# final.net
KiCad netlist of a schematic drawn in Altium Designer
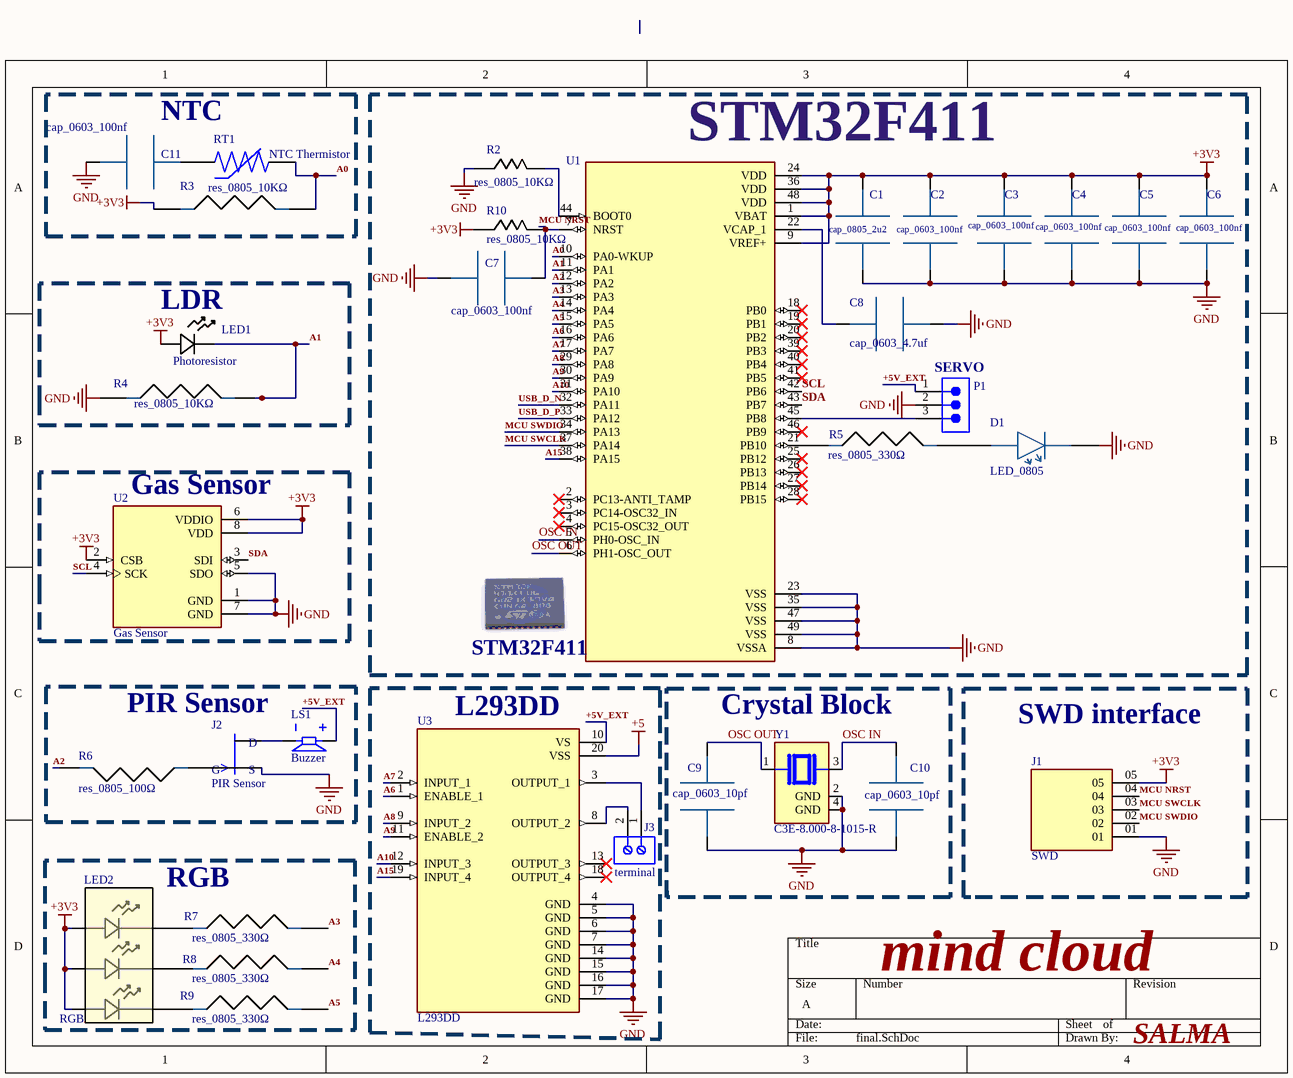
[diagram p0: final.SchDoc]

(export (version "E")
  (design (tool "Eeschema 10.0.6"))
  (components
    (comp (ref "C1")
      (value "cap_0805_2u2")
      (footprint "capa0805")
      (fields (field (name "MFR") "Samsung Electro-Mechanics") (field (name "MFR PART") "CL10A225KO8NNNC"))
      (libsource (lib "STM32") (part "cap_0805_2u2"))
    )
    (comp (ref "C2")
      (value "cap_0603_100nf")
      (footprint "capa0805")
      (fields (field (name "MFR") "Samsung Electro-Mechanics") (field (name "MFR PART") "CL10B104KB8NNNC"))
      (libsource (lib "STM32") (part "cap_0603_100nf"))
    )
    (comp (ref "C3")
      (value "cap_0603_100nf")
      (footprint "capa0805")
      (fields (field (name "MFR") "Samsung Electro-Mechanics") (field (name "MFR PART") "CL10B104KB8NNNC"))
      (libsource (lib "STM32") (part "cap_0603_100nf"))
    )
    (comp (ref "C4")
      (value "cap_0603_100nf")
      (footprint "capa0805")
      (fields (field (name "MFR") "Samsung Electro-Mechanics") (field (name "MFR PART") "CL10B104KB8NNNC"))
      (libsource (lib "STM32") (part "cap_0603_100nf"))
    )
    (comp (ref "C5")
      (value "cap_0603_100nf")
      (footprint "capa0805")
      (fields (field (name "MFR") "Samsung Electro-Mechanics") (field (name "MFR PART") "CL10B104KB8NNNC"))
      (libsource (lib "STM32") (part "cap_0603_100nf"))
    )
    (comp (ref "C6")
      (value "cap_0603_100nf")
      (footprint "capa0805")
      (fields (field (name "MFR") "Samsung Electro-Mechanics") (field (name "MFR PART") "CL10B104KB8NNNC"))
      (libsource (lib "STM32") (part "cap_0603_100nf"))
    )
    (comp (ref "C7")
      (value "cap_0603_100nf")
      (footprint "capa0805")
      (fields (field (name "MFR") "Samsung Electro-Mechanics") (field (name "MFR PART") "CL10B104KB8NNNC"))
      (libsource (lib "STM32") (part "cap_0603_100nf"))
    )
    (comp (ref "C8")
      (value "cap_0603_4.7uf")
      (footprint "capa0805")
      (fields (field (name "MFR") "Samsung Electro-Mechanics") (field (name "MFR PART") "CL10A475KP8NNNC"))
      (libsource (lib "STM32") (part "cap_0603_4.7uf"))
    )
    (comp (ref "C9")
      (value "cap_0603_10pf")
      (footprint "capa0805")
      (fields (field (name "MFR") "Samsung Electro-Mechanics") (field (name "MFR PART") "CL10C100JB8NNNC"))
      (libsource (lib "STM32") (part "cap_0603_10pf"))
    )
    (comp (ref "C10")
      (value "cap_0603_10pf")
      (footprint "capa0805")
      (fields (field (name "MFR") "Samsung Electro-Mechanics") (field (name "MFR PART") "CL10C100JB8NNNC"))
      (libsource (lib "STM32") (part "cap_0603_10pf"))
    )
    (comp (ref "C11")
      (value "cap_0603_100nf")
      (footprint "capa0805")
      (fields (field (name "MFR") "Samsung Electro-Mechanics") (field (name "MFR PART") "CL10B104KB8NNNC"))
      (libsource (lib "STM32") (part "cap_0603_100nf"))
    )
    (comp (ref "D1")
      (value "LED_0805")
      (footprint "LED_0805")
      (fields (field (name "MFR") "YONGYUTAI") (field (name "MFR PART") "YLED0805R"))
      (libsource (lib "Schlib final") (part "LED_0805"))
    )
    (comp (ref "J1")
      (value "SWD")
      (footprint "SAMTEC_MTSW-105-07-T-S-165")
      (fields (field (name "MFR") "Samtec") (field (name "MFR PART") "MTSW-105-07-T-S-165"))
      (libsource (lib "STM32") (part "MTSW-105-07-T-S-165"))
    )
    (comp (ref "J2")
      (value "PIR Sensor")
      (footprint "PIR Sensor")
      (fields (field (name "MFR") "Zilog") (field (name "MFR PART") "ZRE200GE"))
      (libsource (lib "Schlib final") (part "PIR Sensor"))
    )
    (comp (ref "J3")
      (value "terminal")
      (footprint "691253900002")
      (description "Terminal Block, 7.5MM Pitch, Vertical, Rising Cage Clamp, 12-30 AWG, 2 Pin")
      (libsource (lib "Altium Content Vault") (part "TBL - 1R - 02P - Screw"))
    )
    (comp (ref "LED1")
      (value "Photoresistor")
      (footprint "Photoresistor")
      (fields (field (name "MFR") "JCHL") (field (name "MFR PART") "GL5528(10-20)"))
      (libsource (lib "Schlib final") (part "Photoresistor"))
    )
    (comp (ref "LED2")
      (value "RGB")
      (footprint "RGB")
      (fields (field (name "MFR") "Broadcom") (field (name "MFR PART") "ASMT-YTD7-0AA02"))
      (libsource (lib "Schlib final") (part "RGB"))
    )
    (comp (ref "LS1")
      (value "Buzzer")
      (footprint "Buzzer")
      (fields (field (name "MFR") "CUI") (field (name "MFR PART") "CMI-1210-5-95T"))
      (libsource (lib "Schlib final") (part "Buzzer"))
    )
    (comp (ref "P1")
      (value "SERVO")
      (footprint "691386700003")
      (description "Terminal Block, 5.00MM, Male Pcb Horizontal/vertical Cab Divisible, 3 Pins")
      (fields (field (name "VOLTAGE") "300V"))
      (libsource (lib "Altium Content Vault") (part "TBL - 1R - 03P - Male"))
    )
    (comp (ref "R2")
      (value "res_0805_10KΩ")
      (footprint "Res_0805")
      (fields (field (name "MFR") "YAGEO") (field (name "MFR PART") "RC0603FR-0710KL"))
      (libsource (lib "Schlib final") (part "res_0805_10KΩ"))
    )
    (comp (ref "R3")
      (value "res_0805_10KΩ")
      (footprint "Res_0805")
      (fields (field (name "MFR") "YAGEO") (field (name "MFR PART") "RC0603FR-0710KL"))
      (libsource (lib "STM32") (part "res_0805_10KΩ"))
    )
    (comp (ref "R4")
      (value "res_0805_10KΩ")
      (footprint "Res_0805")
      (fields (field (name "MFR") "YAGEO") (field (name "MFR PART") "RC0603FR-0710KL"))
      (libsource (lib "STM32") (part "res_0805_10KΩ"))
    )
    (comp (ref "R5")
      (value "res_0805_330Ω")
      (footprint "Res_0805")
      (fields (field (name "MFR") "UNI-ROYAL") (field (name "MFR PART") "0805W8F3300T5E"))
      (libsource (lib "Schlib final") (part "res_0805_330Ω"))
    )
    (comp (ref "R6")
      (value "res_0805_100Ω")
      (footprint "Res_0805")
      (fields (field (name "MFR") "YAGEO") (field (name "MFR PART") "RC0805FR-07100RL"))
      (libsource (lib "Schlib final") (part "res_0805_100Ω"))
    )
    (comp (ref "R7")
      (value "res_0805_330Ω")
      (footprint "Res_0805")
      (fields (field (name "MFR") "UNI-ROYAL") (field (name "MFR PART") "0805W8F3300T5E"))
      (libsource (lib "Schlib final") (part "res_0805_330Ω"))
    )
    (comp (ref "R8")
      (value "res_0805_330Ω")
      (footprint "Res_0805")
      (fields (field (name "MFR") "UNI-ROYAL") (field (name "MFR PART") "0805W8F3300T5E"))
      (libsource (lib "Schlib final") (part "res_0805_330Ω"))
    )
    (comp (ref "R9")
      (value "res_0805_330Ω")
      (footprint "Res_0805")
      (fields (field (name "MFR") "UNI-ROYAL") (field (name "MFR PART") "0805W8F3300T5E"))
      (libsource (lib "Schlib final") (part "res_0805_330Ω"))
    )
    (comp (ref "R10")
      (value "res_0805_10KΩ")
      (footprint "Res_0805")
      (fields (field (name "MFR") "YAGEO") (field (name "MFR PART") "RC0603FR-0710KL"))
      (libsource (lib "Schlib final") (part "res_0805_10KΩ"))
    )
    (comp (ref "RT1")
      (value "NTC Thermistor")
      (footprint "NTC Thermistor")
      (fields (field (name "MFR") "muRata") (field (name "MFR PART") "NCU15WF104D60RC"))
      (libsource (lib "Schlib final") (part "NTC Thermistor"))
    )
    (comp (ref "U1")
      (value "STM32F411")
      (footprint "STM32F411")
      (fields (field (name "MFR") "ST") (field (name "MFR PART") "STM32F411CEU6"))
      (libsource (lib "STM32") (part "STM32F411"))
    )
    (comp (ref "U2")
      (value "Gas Sensor")
      (footprint "Gas Sensor")
      (fields (field (name "MFR") "Bosch") (field (name "MFR PART") "BME688"))
      (libsource (lib "Schlib final") (part "Gas Sensor"))
    )
    (comp (ref "U3")
      (value "L293DD")
      (footprint "L293DD")
      (fields (field (name "MFR") "ST"))
      (libsource (lib "Schlib final") (part "L293DD"))
    )
    (comp (ref "Y1")
      (value "C3E-8.000-8-1015-R")
      (footprint "C3E-8.000-8-1015-R")
      (fields (field (name "MFR") "AKER"))
      (libsource (lib "STM32") (part "C3E-8.000-8-1015-R"))
    )
  )
  (nets
    (net (code "1") (name "+3V3") (class "Default")
      (node (ref "C1") (pin "2") (pinfunction "2_2") (pintype "passive"))
      (node (ref "C2") (pin "2") (pinfunction "2_2") (pintype "passive"))
      (node (ref "C3") (pin "2") (pinfunction "2_2") (pintype "passive"))
      (node (ref "C4") (pin "2") (pinfunction "2_2") (pintype "passive"))
      (node (ref "C5") (pin "2") (pinfunction "2_2") (pintype "passive"))
      (node (ref "C6") (pin "2") (pinfunction "2_2") (pintype "passive"))
      (node (ref "J1") (pin "05") (pinfunction "05_05") (pintype "passive"))
      (node (ref "LED1") (pin "2") (pinfunction "ANODE_2") (pintype "passive"))
      (node (ref "LED2") (pin "1") (pinfunction "1_1") (pintype "passive"))
      (node (ref "LED2") (pin "2") (pinfunction "2_2") (pintype "passive"))
      (node (ref "LED2") (pin "3") (pinfunction "3_3") (pintype "passive"))
      (node (ref "R10") (pin "1") (pinfunction "1_1") (pintype "passive"))
      (node (ref "R3") (pin "1") (pinfunction "1_1") (pintype "passive"))
      (node (ref "U1") (pin "1") (pinfunction "VBAT_1") (pintype "power_in"))
      (node (ref "U1") (pin "24") (pinfunction "VDD_24") (pintype "power_in"))
      (node (ref "U1") (pin "36") (pinfunction "VDD_36") (pintype "power_in"))
      (node (ref "U1") (pin "48") (pinfunction "VDD_48") (pintype "power_in"))
      (node (ref "U1") (pin "9") (pinfunction "VREF+_9") (pintype "power_in"))
      (node (ref "U2") (pin "2") (pinfunction "CSB_2") (pintype "input"))
      (node (ref "U2") (pin "6") (pinfunction "VDDIO_6") (pintype "power_in"))
      (node (ref "U2") (pin "8") (pinfunction "VDD_8") (pintype "power_in"))
    )
    (net (code "2") (name "+5") (class "Default")
      (node (ref "U3") (pin "20") (pinfunction "VSS_20") (pintype "power_in"))
    )
    (net (code "3") (name "/+5V_EXT") (class "Default")
      (node (ref "LS1") (pin "P") (pinfunction "P_P") (pintype "passive"))
      (node (ref "P1") (pin "1") (pinfunction "1_1") (pintype "passive"))
      (node (ref "U3") (pin "10") (pinfunction "VS_10") (pintype "power_in"))
    )
    (net (code "4") (name "/A0") (class "Default")
      (node (ref "R3") (pin "2") (pinfunction "2_2") (pintype "passive"))
      (node (ref "RT1") (pin "2") (pinfunction "2_2") (pintype "passive"))
      (node (ref "U1") (pin "10") (pinfunction "PA0-WKUP_10") (pintype "bidirectional"))
    )
    (net (code "5") (name "/A1") (class "Default")
      (node (ref "LED1") (pin "1") (pinfunction "CATHODE_1") (pintype "passive"))
      (node (ref "R4") (pin "2") (pinfunction "2_2") (pintype "passive"))
      (node (ref "U1") (pin "11") (pinfunction "PA1_11") (pintype "bidirectional"))
    )
    (net (code "6") (name "/A2") (class "Default")
      (node (ref "R6") (pin "2") (pinfunction "2_2") (pintype "passive"))
      (node (ref "U1") (pin "12") (pinfunction "PA2_12") (pintype "bidirectional"))
    )
    (net (code "7") (name "/A3") (class "Default")
      (node (ref "R7") (pin "2") (pinfunction "2_2") (pintype "passive"))
      (node (ref "U1") (pin "13") (pinfunction "PA3_13") (pintype "bidirectional"))
    )
    (net (code "8") (name "/A4") (class "Default")
      (node (ref "R8") (pin "2") (pinfunction "2_2") (pintype "passive"))
      (node (ref "U1") (pin "14") (pinfunction "PA4_14") (pintype "bidirectional"))
    )
    (net (code "9") (name "/A5") (class "Default")
      (node (ref "R9") (pin "2") (pinfunction "2_2") (pintype "passive"))
      (node (ref "U1") (pin "15") (pinfunction "PA5_15") (pintype "bidirectional"))
    )
    (net (code "10") (name "/A6") (class "Default")
      (node (ref "U1") (pin "16") (pinfunction "PA6_16") (pintype "bidirectional"))
      (node (ref "U3") (pin "1") (pinfunction "ENABLE_1_1") (pintype "input"))
    )
    (net (code "11") (name "/A7") (class "Default")
      (node (ref "U1") (pin "17") (pinfunction "PA7_17") (pintype "bidirectional"))
      (node (ref "U3") (pin "2") (pinfunction "INPUT_1_2") (pintype "input"))
    )
    (net (code "12") (name "/A8") (class "Default")
      (node (ref "U1") (pin "29") (pinfunction "PA8_29") (pintype "bidirectional"))
      (node (ref "U3") (pin "9") (pinfunction "INPUT_2_9") (pintype "input"))
    )
    (net (code "13") (name "/A9") (class "Default")
      (node (ref "U1") (pin "30") (pinfunction "PA9_30") (pintype "bidirectional"))
      (node (ref "U3") (pin "11") (pinfunction "ENABLE_2_11") (pintype "input"))
    )
    (net (code "14") (name "/A10") (class "Default")
      (node (ref "U1") (pin "31") (pinfunction "PA10_31") (pintype "bidirectional"))
      (node (ref "U3") (pin "12") (pinfunction "INPUT_3_12") (pintype "input"))
    )
    (net (code "15") (name "/A15") (class "Default")
      (node (ref "U1") (pin "38") (pinfunction "PA15_38") (pintype "bidirectional"))
      (node (ref "U3") (pin "19") (pinfunction "INPUT_4_19") (pintype "input"))
    )
    (net (code "16") (name "/MCU NRST") (class "Default")
      (node (ref "C7") (pin "2") (pinfunction "2_2") (pintype "passive"))
      (node (ref "J1") (pin "04") (pinfunction "04_04") (pintype "passive"))
      (node (ref "R10") (pin "2") (pinfunction "2_2") (pintype "passive"))
      (node (ref "U1") (pin "7") (pinfunction "NRST_7") (pintype "bidirectional"))
    )
    (net (code "17") (name "/MCU SWCLK") (class "Default")
      (node (ref "J1") (pin "03") (pinfunction "03_03") (pintype "passive"))
      (node (ref "U1") (pin "37") (pinfunction "PA14_37") (pintype "bidirectional"))
    )
    (net (code "18") (name "/MCU SWDIO") (class "Default")
      (node (ref "J1") (pin "02") (pinfunction "02_02") (pintype "passive"))
      (node (ref "U1") (pin "34") (pinfunction "PA13_34") (pintype "bidirectional"))
    )
    (net (code "19") (name "/OSC IN") (class "Default")
      (node (ref "C10") (pin "2") (pinfunction "2_2") (pintype "passive"))
      (node (ref "U1") (pin "5") (pinfunction "PH0-OSC_IN_5") (pintype "bidirectional"))
      (node (ref "Y1") (pin "3") (pinfunction "2_3") (pintype "passive"))
    )
    (net (code "20") (name "/OSC OUT") (class "Default")
      (node (ref "C9") (pin "2") (pinfunction "2_2") (pintype "passive"))
      (node (ref "U1") (pin "6") (pinfunction "PH1-OSC_OUT_6") (pintype "bidirectional"))
      (node (ref "Y1") (pin "1") (pinfunction "1_1") (pintype "passive"))
    )
    (net (code "21") (name "/SCL") (class "Default")
      (node (ref "U1") (pin "42") (pinfunction "PB6_42") (pintype "bidirectional"))
      (node (ref "U2") (pin "4") (pinfunction "SCK_4") (pintype "input"))
    )
    (net (code "22") (name "/SDA") (class "Default")
      (node (ref "U1") (pin "43") (pinfunction "PB7_43") (pintype "bidirectional"))
      (node (ref "U2") (pin "3") (pinfunction "SDI_3") (pintype "bidirectional"))
    )
    (net (code "23") (name "/USB_D_N") (class "Default")
      (node (ref "U1") (pin "32") (pinfunction "PA11_32") (pintype "bidirectional"))
    )
    (net (code "24") (name "/USB_D_P") (class "Default")
      (node (ref "U1") (pin "33") (pinfunction "PA12_33") (pintype "bidirectional"))
    )
    (net (code "25") (name "GND") (class "Default")
      (node (ref "C1") (pin "1") (pinfunction "1_1") (pintype "passive"))
      (node (ref "C10") (pin "1") (pinfunction "1_1") (pintype "passive"))
      (node (ref "C11") (pin "1") (pinfunction "1_1") (pintype "passive"))
      (node (ref "C2") (pin "1") (pinfunction "1_1") (pintype "passive"))
      (node (ref "C3") (pin "1") (pinfunction "1_1") (pintype "passive"))
      (node (ref "C4") (pin "1") (pinfunction "1_1") (pintype "passive"))
      (node (ref "C5") (pin "1") (pinfunction "1_1") (pintype "passive"))
      (node (ref "C6") (pin "1") (pinfunction "1_1") (pintype "passive"))
      (node (ref "C7") (pin "1") (pinfunction "1_1") (pintype "passive"))
      (node (ref "C8") (pin "2") (pinfunction "2_2") (pintype "passive"))
      (node (ref "C9") (pin "1") (pinfunction "1_1") (pintype "passive"))
      (node (ref "D1") (pin "2") (pinfunction "2_2") (pintype "passive"))
      (node (ref "J1") (pin "01") (pinfunction "01_01") (pintype "passive"))
      (node (ref "J2") (pin "2") (pinfunction "S_2") (pintype "passive"))
      (node (ref "P1") (pin "2") (pinfunction "2_2") (pintype "passive"))
      (node (ref "R2") (pin "1") (pinfunction "1_1") (pintype "passive"))
      (node (ref "R4") (pin "1") (pinfunction "1_1") (pintype "passive"))
      (node (ref "U1") (pin "23") (pinfunction "VSS_23") (pintype "power_in"))
      (node (ref "U1") (pin "35") (pinfunction "VSS_35") (pintype "power_in"))
      (node (ref "U1") (pin "47") (pinfunction "VSS_47") (pintype "power_in"))
      (node (ref "U1") (pin "49") (pinfunction "VSS_49") (pintype "power_in"))
      (node (ref "U1") (pin "8") (pinfunction "VSSA_8") (pintype "power_in"))
      (node (ref "U2") (pin "1") (pinfunction "GND_1") (pintype "power_in"))
      (node (ref "U2") (pin "5") (pinfunction "SDO_5") (pintype "bidirectional"))
      (node (ref "U2") (pin "7") (pinfunction "GND_7") (pintype "power_in"))
      (node (ref "U3") (pin "14") (pinfunction "GND_14") (pintype "power_in"))
      (node (ref "U3") (pin "15") (pinfunction "GND_15") (pintype "power_in"))
      (node (ref "U3") (pin "16") (pinfunction "GND_16") (pintype "power_in"))
      (node (ref "U3") (pin "17") (pinfunction "GND_17") (pintype "power_in"))
      (node (ref "U3") (pin "4") (pinfunction "GND_4") (pintype "power_in"))
      (node (ref "U3") (pin "5") (pinfunction "GND_5") (pintype "power_in"))
      (node (ref "U3") (pin "6") (pinfunction "GND_6") (pintype "power_in"))
      (node (ref "U3") (pin "7") (pinfunction "GND_7") (pintype "power_in"))
      (node (ref "Y1") (pin "2") (pinfunction "GND_2") (pintype "power_in"))
      (node (ref "Y1") (pin "4") (pinfunction "GND_4") (pintype "power_in"))
    )
    (net (code "26") (name "Net-(D1-Pad1)") (class "Default")
      (node (ref "D1") (pin "1") (pinfunction "1_1") (pintype "passive"))
      (node (ref "R5") (pin "2") (pinfunction "2_2") (pintype "passive"))
    )
    (net (code "27") (name "Net-(J2-D)") (class "Default")
      (node (ref "J2") (pin "1") (pinfunction "D_1") (pintype "passive"))
      (node (ref "LS1") (pin "N") (pinfunction "N_N") (pintype "passive"))
    )
    (net (code "28") (name "Net-(LED2-Pad4)") (class "Default")
      (node (ref "LED2") (pin "4") (pinfunction "4_4") (pintype "passive"))
      (node (ref "R9") (pin "1") (pinfunction "1_1") (pintype "passive"))
    )
    (net (code "29") (name "Net-(LED2-Pad5)") (class "Default")
      (node (ref "LED2") (pin "5") (pinfunction "5_5") (pintype "passive"))
      (node (ref "R8") (pin "1") (pinfunction "1_1") (pintype "passive"))
    )
    (net (code "30") (name "Net-(LED2-Pad6)") (class "Default")
      (node (ref "LED2") (pin "6") (pinfunction "6_6") (pintype "passive"))
      (node (ref "R7") (pin "1") (pinfunction "1_1") (pintype "passive"))
    )
    (net (code "31") (name "Net-(U1-BOOT0)") (class "Default")
      (node (ref "R2") (pin "2") (pinfunction "2_2") (pintype "passive"))
      (node (ref "U1") (pin "44") (pinfunction "BOOT0_44") (pintype "input"))
    )
    (net (code "32") (name "Net-(U1-PB8)") (class "Default")
      (node (ref "P1") (pin "3") (pinfunction "3_3") (pintype "passive"))
      (node (ref "U1") (pin "45") (pinfunction "PB8_45") (pintype "bidirectional"))
    )
    (net (code "33") (name "Net-(U1-PB10)") (class "Default")
      (node (ref "R5") (pin "1") (pinfunction "1_1") (pintype "passive"))
      (node (ref "U1") (pin "21") (pinfunction "PB10_21") (pintype "bidirectional"))
    )
    (net (code "34") (name "Net-(U1-VCAP_1)") (class "Default")
      (node (ref "C8") (pin "1") (pinfunction "1_1") (pintype "passive"))
      (node (ref "U1") (pin "22") (pinfunction "VCAP_1_22") (pintype "power_in"))
    )
    (net (code "35") (name "Net-(U3-OUTPUT_1)") (class "Default")
      (node (ref "J3") (pin "1") (pinfunction "1_1") (pintype "passive"))
      (node (ref "U3") (pin "3") (pinfunction "OUTPUT_1_3") (pintype "output"))
    )
    (net (code "36") (name "Net-(U3-OUTPUT_2)") (class "Default")
      (node (ref "J3") (pin "2") (pinfunction "2_2") (pintype "passive"))
      (node (ref "U3") (pin "8") (pinfunction "OUTPUT_2_8") (pintype "output"))
    )
    (net (code "37") (name "unconnected-(C11-Pad2)") (class "Default")
      (node (ref "C11") (pin "2") (pinfunction "2_2") (pintype "passive"))
    )
    (net (code "38") (name "unconnected-(J2-G-Pad3)") (class "Default")
      (node (ref "J2") (pin "3") (pinfunction "G_3") (pintype "passive"))
    )
    (net (code "39") (name "unconnected-(R6-Pad1)") (class "Default")
      (node (ref "R6") (pin "1") (pinfunction "1_1") (pintype "passive"))
    )
    (net (code "40") (name "unconnected-(RT1-Pad1)") (class "Default")
      (node (ref "RT1") (pin "1") (pinfunction "1_1") (pintype "passive"))
    )
    (net (code "41") (name "unconnected-(U1-PB0-Pad18)") (class "Default")
      (node (ref "U1") (pin "18") (pinfunction "PB0_18") (pintype "bidirectional+no_connect"))
    )
    (net (code "42") (name "unconnected-(U1-PB1-Pad19)") (class "Default")
      (node (ref "U1") (pin "19") (pinfunction "PB1_19") (pintype "bidirectional+no_connect"))
    )
    (net (code "43") (name "unconnected-(U1-PB2-Pad20)") (class "Default")
      (node (ref "U1") (pin "20") (pinfunction "PB2_20") (pintype "bidirectional+no_connect"))
    )
    (net (code "44") (name "unconnected-(U1-PB3-Pad39)") (class "Default")
      (node (ref "U1") (pin "39") (pinfunction "PB3_39") (pintype "bidirectional+no_connect"))
    )
    (net (code "45") (name "unconnected-(U1-PB4-Pad40)") (class "Default")
      (node (ref "U1") (pin "40") (pinfunction "PB4_40") (pintype "bidirectional+no_connect"))
    )
    (net (code "46") (name "unconnected-(U1-PB5-Pad41)") (class "Default")
      (node (ref "U1") (pin "41") (pinfunction "PB5_41") (pintype "bidirectional+no_connect"))
    )
    (net (code "47") (name "unconnected-(U1-PB9-Pad46)") (class "Default")
      (node (ref "U1") (pin "46") (pinfunction "PB9_46") (pintype "bidirectional+no_connect"))
    )
    (net (code "48") (name "unconnected-(U1-PB12-Pad25)") (class "Default")
      (node (ref "U1") (pin "25") (pinfunction "PB12_25") (pintype "bidirectional+no_connect"))
    )
    (net (code "49") (name "unconnected-(U1-PB13-Pad26)") (class "Default")
      (node (ref "U1") (pin "26") (pinfunction "PB13_26") (pintype "bidirectional+no_connect"))
    )
    (net (code "50") (name "unconnected-(U1-PB14-Pad27)") (class "Default")
      (node (ref "U1") (pin "27") (pinfunction "PB14_27") (pintype "bidirectional+no_connect"))
    )
    (net (code "51") (name "unconnected-(U1-PB15-Pad28)") (class "Default")
      (node (ref "U1") (pin "28") (pinfunction "PB15_28") (pintype "bidirectional+no_connect"))
    )
    (net (code "52") (name "unconnected-(U1-PC13-ANTI_TAMP-Pad2)") (class "Default")
      (node (ref "U1") (pin "2") (pinfunction "PC13-ANTI_TAMP_2") (pintype "bidirectional+no_connect"))
    )
    (net (code "53") (name "unconnected-(U1-PC14-OSC32_IN-Pad3)") (class "Default")
      (node (ref "U1") (pin "3") (pinfunction "PC14-OSC32_IN_3") (pintype "bidirectional+no_connect"))
    )
    (net (code "54") (name "unconnected-(U1-PC15-OSC32_OUT-Pad4)") (class "Default")
      (node (ref "U1") (pin "4") (pinfunction "PC15-OSC32_OUT_4") (pintype "bidirectional+no_connect"))
    )
    (net (code "55") (name "unconnected-(U3-OUTPUT_3-Pad13)") (class "Default")
      (node (ref "U3") (pin "13") (pinfunction "OUTPUT_3_13") (pintype "output+no_connect"))
    )
    (net (code "56") (name "unconnected-(U3-OUTPUT_4-Pad18)") (class "Default")
      (node (ref "U3") (pin "18") (pinfunction "OUTPUT_4_18") (pintype "output+no_connect"))
    )
  )
)
